# OPID_351_5V_Step-down_regulator.net
KiCad netlist of a schematic drawn in Altium Designer
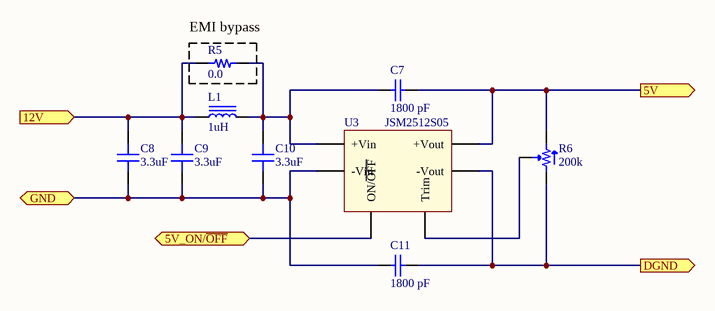
[diagram p0: OPID[351] 5V Step-down regulator.SchDoc]

(export (version "E")
  (design (tool "Eeschema 10.0.6"))
  (components
    (comp (ref "C7")
      (value "1800 pF")
      (footprint "CAP1210(3225)")
      (fields (field (name "PART NUMBER") "C1210C182JGRACTU") (field (name "TOLERANCE") "± 5%"))
      (libsource (lib "Vortex-component-database") (part "Capacitor"))
    )
    (comp (ref "C8")
      (value "3.3uF")
      (footprint "CAP 1210/3225 - 2.0MM")
      (description "CAP CER 3.3UF 25V X8L 1210")
      (fields (field (name "PART NUMBER") "C1210C335K3NACTU") (field (name "MANUFACTURER") "Kemet"))
      (libsource (lib "Celestial Library Database") (part "Capacitor"))
    )
    (comp (ref "C9")
      (value "3.3uF")
      (footprint "CAP 1210/3225 - 2.0MM")
      (description "CAP CER 3.3UF 25V X8L 1210")
      (fields (field (name "PART NUMBER") "C1210C335K3NACTU") (field (name "MANUFACTURER") "Kemet"))
      (libsource (lib "Celestial Library Database") (part "Capacitor"))
    )
    (comp (ref "C10")
      (value "3.3uF")
      (footprint "CAP 1210/3225 - 2.0MM")
      (description "CAP CER 3.3UF 25V X8L 1210")
      (fields (field (name "PART NUMBER") "C1210C335K3NACTU") (field (name "MANUFACTURER") "Kemet"))
      (libsource (lib "Celestial Library Database") (part "Capacitor"))
    )
    (comp (ref "C11")
      (value "1800 pF")
      (footprint "CAP1210(3225)")
      (fields (field (name "PART NUMBER") "C1210C182JGRACTU") (field (name "TOLERANCE") "± 5%"))
      (libsource (lib "Vortex-component-database") (part "Capacitor"))
    )
    (comp (ref "L1")
      (value "1uH")
      (footprint "TDK VLS252012CX")
      (description "FIXED IND 1UH 2.55A 62 MOHM SMD")
      (fields (field (name "PART NUMBER") "VLS252012CX-1R0M") (field (name "MANUFACTURER") "TDK Corporation"))
      (libsource (lib "Celestial Library Database") (part "Inductor"))
    )
    (comp (ref "R5")
      (value "0.0")
      (footprint "RES 0805/2012")
      (description "RES SMD 0.0 OHM JUMPER 1/2W 0805")
      (fields (field (name "PART NUMBER") "5106") (field (name "MANUFACTURER") "Keystone Electronics"))
      (libsource (lib "Celestial Library Database") (part "Resistor"))
    )
    (comp (ref "R6")
      (value "200k")
      (footprint "POT PANASONIC EVM2W")
      (description "TRIMMER 200K OHM 0.15W SMD")
      (fields
        (field (name "PART NUMBER") "EVM-2WSX80B25")
        (field (name "MANUFACTURER") "Panasonic Electronic Components")
      )
      (libsource (lib "Celestial Library Database") (part "Potentiometer"))
    )
    (comp (ref "U3")
      (value "JSM2512S05")
      (footprint "JSM2512S05")
      (description "XP Power J Series JSM25 DC/DC Converter")
      (libsource (lib "Vortex-component-database") (part "JSM25_S"))
    )
  )
  (nets
    (net (code "1") (name "/5V") (class "Default")
      (node (ref "C7") (pin "2") (pinfunction "2_2") (pintype "passive"))
      (node (ref "R6") (pin "3") (pinfunction "3_3") (pintype "passive"))
      (node (ref "U3") (pin "3") (pinfunction "+Vout_3") (pintype "passive"))
    )
    (net (code "2") (name "/5V_ON{slash}~{OFF}") (class "Default")
      (node (ref "U3") (pin "6") (pinfunction "ON/~{OFF}_6") (pintype "passive"))
    )
    (net (code "3") (name "/12V") (class "Default")
      (node (ref "C8") (pin "2") (pinfunction "2_2") (pintype "passive"))
      (node (ref "C9") (pin "2") (pinfunction "2_2") (pintype "passive"))
      (node (ref "L1") (pin "1") (pinfunction "1_1") (pintype "passive"))
      (node (ref "R5") (pin "1") (pinfunction "1_1") (pintype "passive"))
    )
    (net (code "4") (name "/DGND") (class "Default")
      (node (ref "C11") (pin "2") (pinfunction "2_2") (pintype "passive"))
      (node (ref "R6") (pin "1") (pinfunction "1_1") (pintype "passive"))
      (node (ref "U3") (pin "5") (pinfunction "-Vout_5") (pintype "passive"))
    )
    (net (code "5") (name "/GND") (class "Default")
      (node (ref "C10") (pin "1") (pinfunction "1_1") (pintype "passive"))
      (node (ref "C11") (pin "1") (pinfunction "1_1") (pintype "passive"))
      (node (ref "C8") (pin "1") (pinfunction "1_1") (pintype "passive"))
      (node (ref "C9") (pin "1") (pinfunction "1_1") (pintype "passive"))
      (node (ref "U3") (pin "2") (pinfunction "-Vin_2") (pintype "passive"))
    )
    (net (code "6") (name "Net-(U3-+Vin)") (class "Default")
      (node (ref "C10") (pin "2") (pinfunction "2_2") (pintype "passive"))
      (node (ref "C7") (pin "1") (pinfunction "1_1") (pintype "passive"))
      (node (ref "L1") (pin "2") (pinfunction "2_2") (pintype "passive"))
      (node (ref "R5") (pin "2") (pinfunction "2_2") (pintype "passive"))
      (node (ref "U3") (pin "1") (pinfunction "+Vin_1") (pintype "passive"))
    )
    (net (code "7") (name "Net-(U3-Trim)") (class "Default")
      (node (ref "R6") (pin "2") (pinfunction "2_2") (pintype "passive"))
      (node (ref "U3") (pin "4") (pinfunction "Trim_4") (pintype "passive"))
    )
  )
)
